# source_eagle.net
KiCad netlist of a schematic drawn in EAGLE
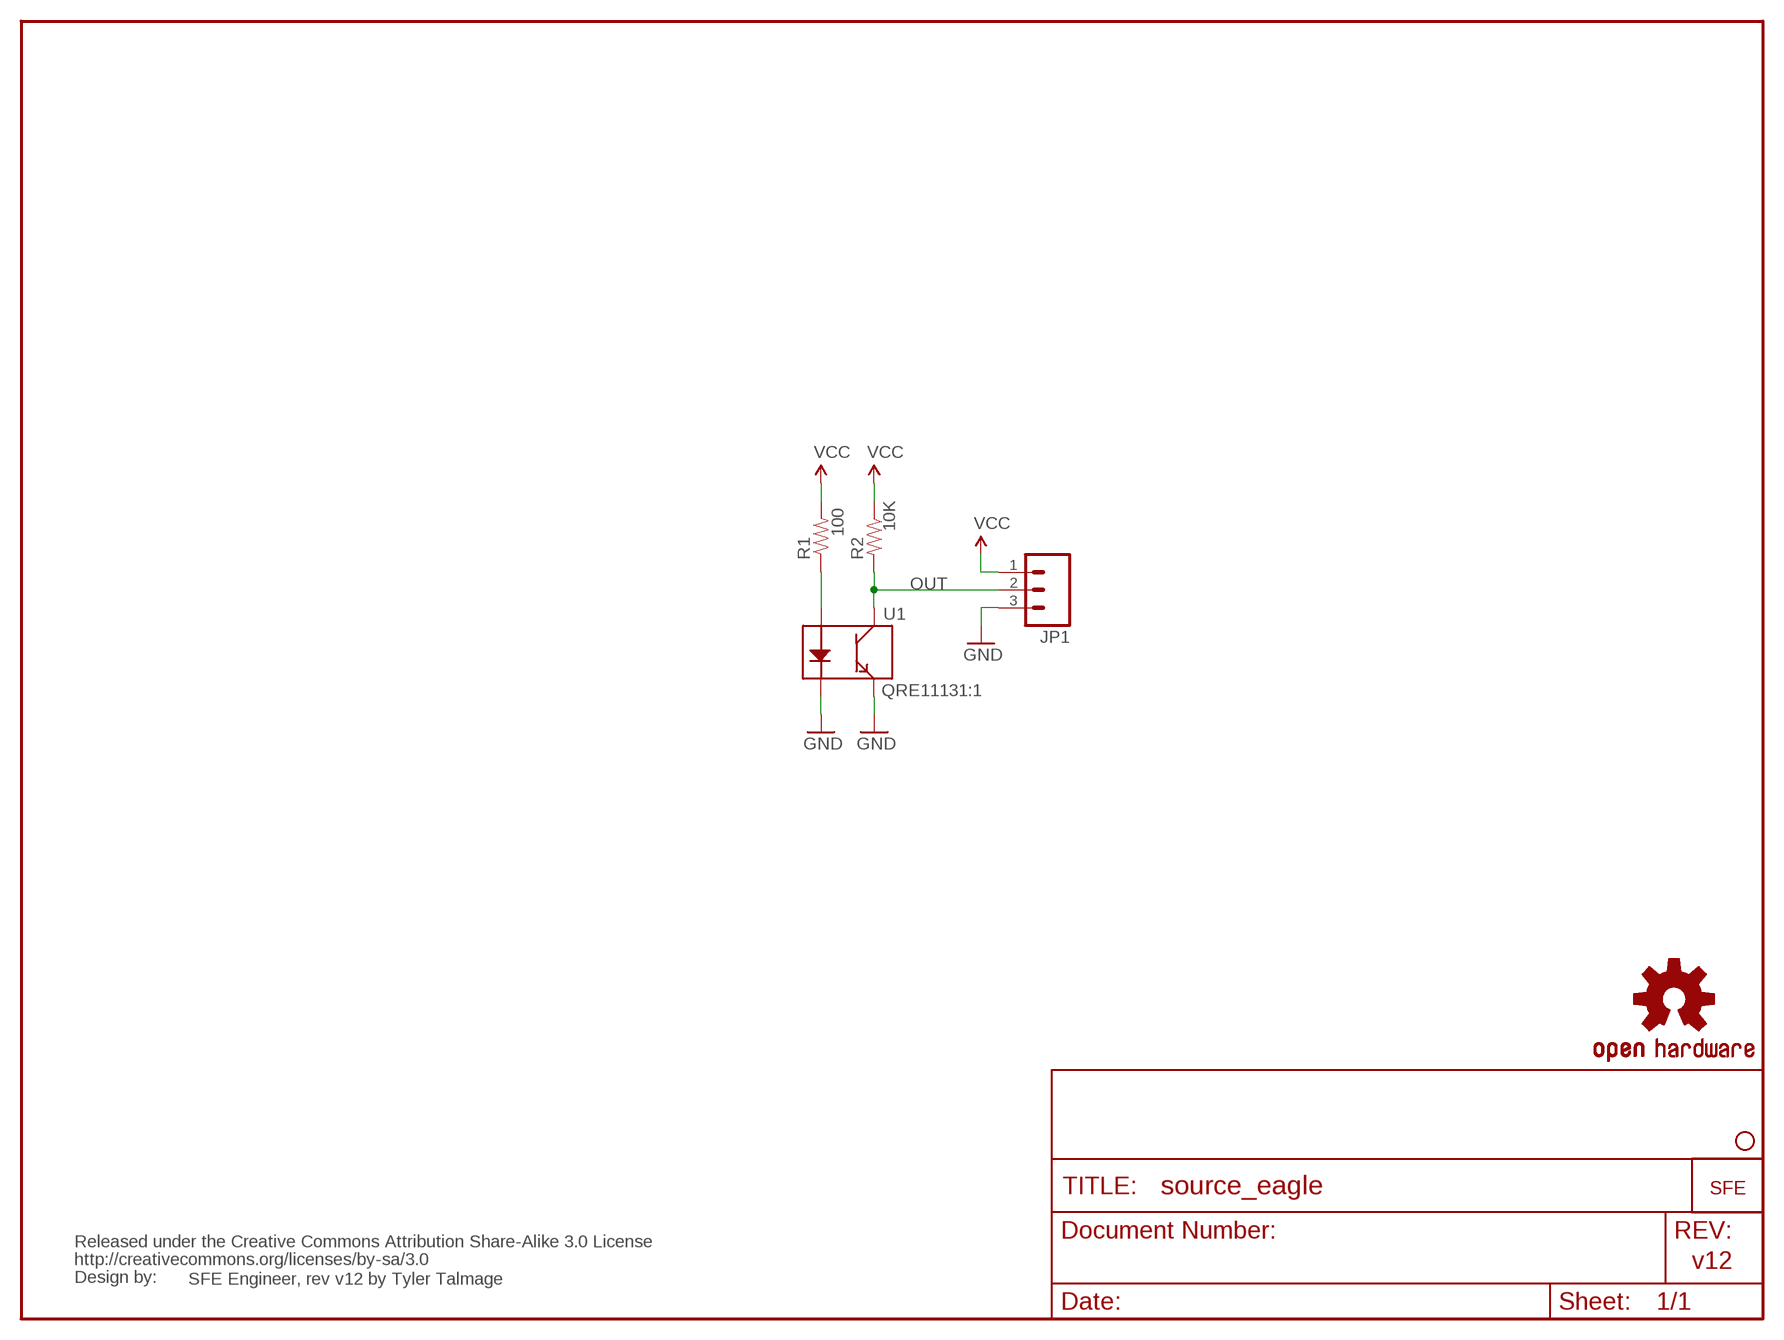
[diagram p0: schematic, sheet 1]

(export (version "E")
  (design (tool "Eeschema 10.0.6"))
  (components
    (comp (ref "CC_TEXT1")
      (value "CREATIVE_COMMONS")
      (footprint "eagle-import:CREATIVE_COMMONS")
      (libsource (lib "eagle-import") (part "CREATIVE_COMMONS"))
    )
    (comp (ref "JP1")
      (value "M03PTH")
      (footprint "eagle-import:1X03")
      (libsource (lib "eagle-import") (part "M03PTH"))
    )
    (comp (ref "JP2")
      (value "LOGO-SFESK")
      (footprint "eagle-import:SFE-LOGO-FLAME")
      (libsource (lib "eagle-import") (part "LOGO-SFESK"))
    )
    (comp (ref "JP3")
      (value "STAND-OFF")
      (footprint "eagle-import:STAND-OFF")
      (libsource (lib "eagle-import") (part "STAND-OFF"))
    )
    (comp (ref "R1")
      (value "100")
      (footprint "eagle-import:0603-RES")
      (libsource (lib "eagle-import") (part "RESISTOR0603-RES"))
    )
    (comp (ref "R2")
      (value "10K")
      (footprint "eagle-import:0603-RES")
      (libsource (lib "eagle-import") (part "RESISTOR0603-RES"))
    )
    (comp (ref "U$1")
      (value "OSHW-LOGOS")
      (footprint "eagle-import:OSHW-LOGO-S")
      (libsource (lib "eagle-import") (part "OSHW-LOGOS"))
    )
    (comp (ref "U1")
      (value "QRE11131:1")
      (footprint "eagle-import:QRE1113-1_1")
      (libsource (lib "eagle-import") (part "QRE11131{colon}1"))
    )
  )
  (nets
    (net (code "1") (name "/OUT") (class "Default")
      (node (ref "JP1") (pin "2") (pinfunction "2_2") (pintype "passive"))
      (node (ref "R2") (pin "2") (pinfunction "2_2") (pintype "passive"))
      (node (ref "U1") (pin "3") (pinfunction "C_3") (pintype "bidirectional"))
    )
    (net (code "2") (name "GND") (class "Default")
      (node (ref "JP1") (pin "3") (pinfunction "3_3") (pintype "passive"))
      (node (ref "U1") (pin "2") (pinfunction "K_2") (pintype "bidirectional"))
      (node (ref "U1") (pin "4") (pinfunction "E_4") (pintype "bidirectional"))
    )
    (net (code "3") (name "Net-(U1-A)") (class "Default")
      (node (ref "R1") (pin "1") (pinfunction "1_1") (pintype "passive"))
      (node (ref "U1") (pin "1") (pinfunction "A_1") (pintype "bidirectional"))
    )
    (net (code "4") (name "VCC") (class "Default")
      (node (ref "JP1") (pin "1") (pinfunction "1_1") (pintype "passive"))
      (node (ref "R1") (pin "2") (pinfunction "2_2") (pintype "passive"))
      (node (ref "R2") (pin "1") (pinfunction "1_1") (pintype "passive"))
    )
  )
)
